# 3_BackBone.net
KiCad netlist of a schematic drawn in Altium Designer
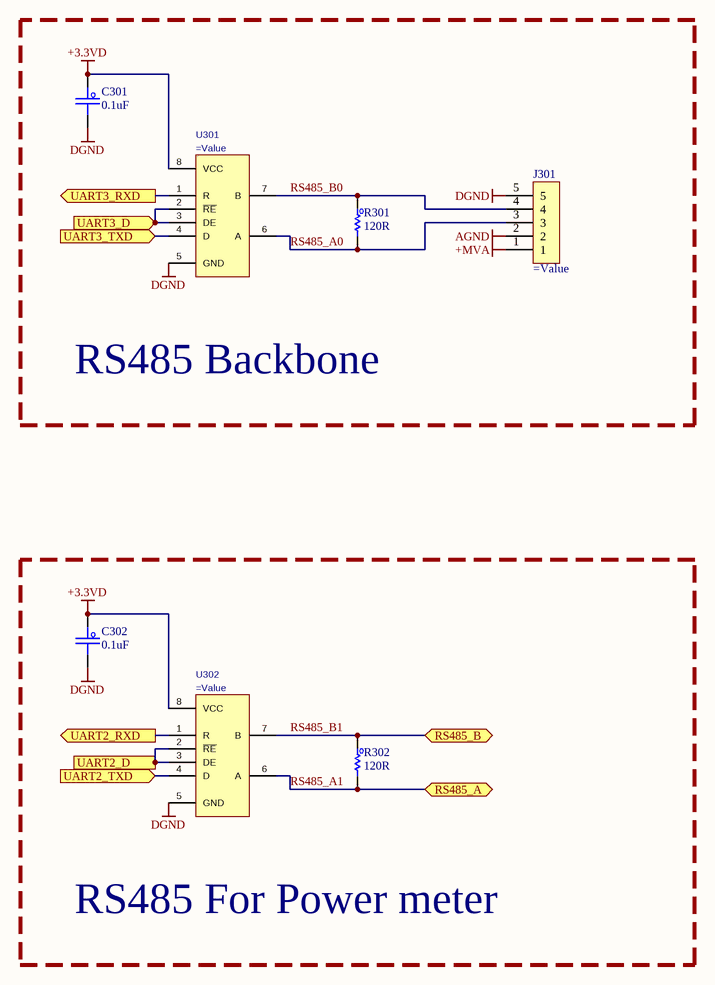
[diagram p0: 3_BackBone.SchDoc]

(export (version "E")
  (design (tool "Eeschema 10.0.6"))
  (components
    (comp (ref "C301")
      (value "0.1uF")
      (footprint "C_0603")
      (description "CAP CER 0.1UF 50V X7R 0603")
      (fields (field (name "MANUFACTURER") "KEMET") (field (name "PARTNUMBER") "C0603C104K5RACTU"))
      (libsource (lib "UUSymbol") (part "C_Capacitor"))
    )
    (comp (ref "C302")
      (value "0.1uF")
      (footprint "C_0603")
      (description "CAP CER 0.1UF 50V X7R 0603")
      (fields (field (name "MANUFACTURER") "KEMET") (field (name "PARTNUMBER") "C0603C104K5RACTU"))
      (libsource (lib "UUSymbol") (part "C_Capacitor"))
    )
    (comp (ref "J301")
      (value "~")
      (footprint "CON_9155005541006")
      (description "CONN SPRING BATTERY 5POS R/A SMD")
      (fields (field (name "PARTNUMBER") "009155005541006") (field (name "MANUFACTURER") "AVX"))
      (libsource (lib "UUSymbol") (part "CON_5P_9155005541006"))
    )
    (comp (ref "R301")
      (value "120R")
      (footprint "R_0603")
      (description "RES SMD 120 OHM 1% 1/3W 0603")
      (fields (field (name "MANUFACTURER") "Vishay Dale") (field (name "PARTNUMBER") "CRCW0603120RFKEAHP"))
      (libsource (lib "UUSymbol") (part "R_Resister"))
    )
    (comp (ref "R302")
      (value "120R")
      (footprint "R_0603")
      (description "RES SMD 120 OHM 1% 1/3W 0603")
      (fields (field (name "MANUFACTURER") "Vishay Dale") (field (name "PARTNUMBER") "CRCW0603120RFKEAHP"))
      (libsource (lib "UUSymbol") (part "R_Resister"))
    )
    (comp (ref "U301")
      (value "~")
      (footprint "D0008A_L")
      (description "IC TRANSCEIVER HALF 1/1 8SOIC")
      (fields (field (name "MANUFACTURER") "Texas Instruments") (field (name "PARTNUMBER") "SN65HVD11DR"))
      (libsource (lib "UUSymbol") (part "IC_TRAN_THVD1505DR"))
    )
    (comp (ref "U302")
      (value "~")
      (footprint "D0008A_L")
      (description "IC TRANSCEIVER HALF 1/1 8SOIC")
      (fields (field (name "MANUFACTURER") "Texas Instruments") (field (name "PARTNUMBER") "SN65HVD11DR"))
      (libsource (lib "UUSymbol") (part "IC_TRAN_THVD1505DR"))
    )
  )
  (nets
    (net (code "1") (name "+3.3VD") (class "Default")
      (node (ref "C301") (pin "1") (pinfunction "1_1") (pintype "passive"))
      (node (ref "C302") (pin "1") (pinfunction "1_1") (pintype "passive"))
      (node (ref "U301") (pin "8") (pinfunction "VCC_8") (pintype "passive"))
      (node (ref "U302") (pin "8") (pinfunction "VCC_8") (pintype "passive"))
    )
    (net (code "2") (name "+MVA") (class "Default")
      (node (ref "J301") (pin "1") (pinfunction "1_1") (pintype "passive"))
    )
    (net (code "3") (name "/RS485_A0") (class "Default")
      (node (ref "J301") (pin "3") (pinfunction "3_3") (pintype "passive"))
      (node (ref "R301") (pin "2") (pinfunction "2_2") (pintype "passive"))
      (node (ref "U301") (pin "6") (pinfunction "A_6") (pintype "passive"))
    )
    (net (code "4") (name "/RS485_A1") (class "Default")
      (node (ref "R302") (pin "2") (pinfunction "2_2") (pintype "passive"))
      (node (ref "U302") (pin "6") (pinfunction "A_6") (pintype "passive"))
    )
    (net (code "5") (name "/RS485_B0") (class "Default")
      (node (ref "J301") (pin "4") (pinfunction "4_4") (pintype "passive"))
      (node (ref "R301") (pin "1") (pinfunction "1_1") (pintype "passive"))
      (node (ref "U301") (pin "7") (pinfunction "B_7") (pintype "passive"))
    )
    (net (code "6") (name "/RS485_B1") (class "Default")
      (node (ref "R302") (pin "1") (pinfunction "1_1") (pintype "passive"))
      (node (ref "U302") (pin "7") (pinfunction "B_7") (pintype "passive"))
    )
    (net (code "7") (name "/UART2_D") (class "Default")
      (node (ref "U302") (pin "2") (pinfunction "~{RE}_2") (pintype "passive"))
      (node (ref "U302") (pin "3") (pinfunction "DE_3") (pintype "passive"))
    )
    (net (code "8") (name "/UART2_RXD") (class "Default")
      (node (ref "U302") (pin "1") (pinfunction "R_1") (pintype "passive"))
    )
    (net (code "9") (name "/UART2_TXD") (class "Default")
      (node (ref "U302") (pin "4") (pinfunction "D_4") (pintype "passive"))
    )
    (net (code "10") (name "/UART3_D") (class "Default")
      (node (ref "U301") (pin "2") (pinfunction "~{RE}_2") (pintype "passive"))
      (node (ref "U301") (pin "3") (pinfunction "DE_3") (pintype "passive"))
    )
    (net (code "11") (name "/UART3_RXD") (class "Default")
      (node (ref "U301") (pin "1") (pinfunction "R_1") (pintype "passive"))
    )
    (net (code "12") (name "/UART3_TXD") (class "Default")
      (node (ref "U301") (pin "4") (pinfunction "D_4") (pintype "passive"))
    )
    (net (code "13") (name "AGND") (class "Default")
      (node (ref "J301") (pin "2") (pinfunction "2_2") (pintype "passive"))
    )
    (net (code "14") (name "DGND") (class "Default")
      (node (ref "C301") (pin "2") (pinfunction "2_2") (pintype "passive"))
      (node (ref "C302") (pin "2") (pinfunction "2_2") (pintype "passive"))
      (node (ref "J301") (pin "5") (pinfunction "5_5") (pintype "passive"))
      (node (ref "U301") (pin "5") (pinfunction "GND_5") (pintype "passive"))
      (node (ref "U302") (pin "5") (pinfunction "GND_5") (pintype "passive"))
    )
  )
)
